# power-management-ctt.net
KiCad netlist of a schematic drawn in Altium Designer
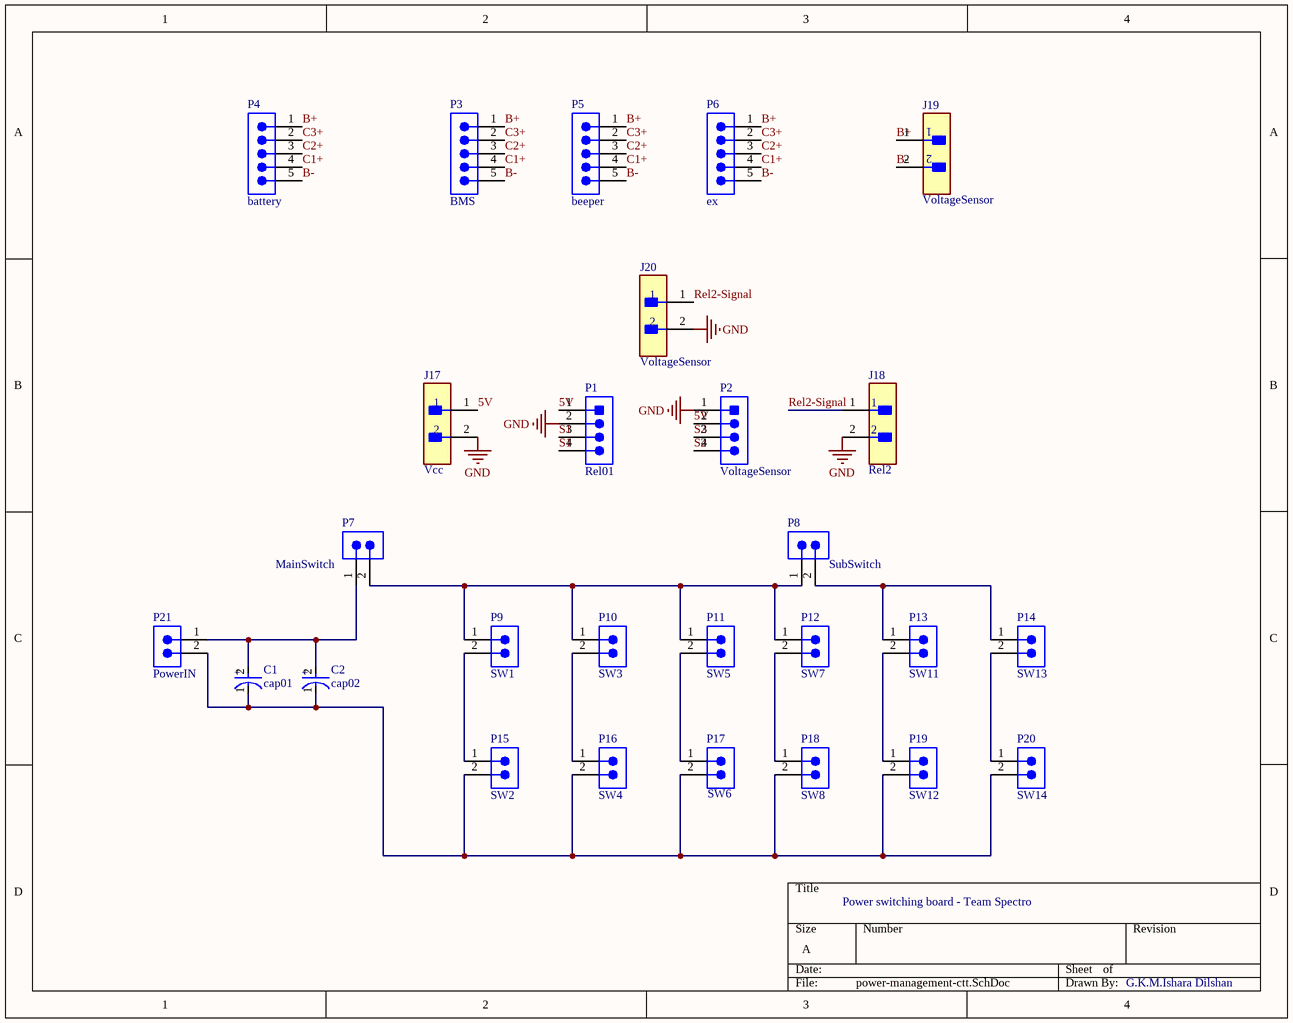
[diagram p0: power-management-ctt.SchDoc]

(export (version "E")
  (design (tool "Eeschema 10.0.6"))
  (components
    (comp (ref "C1")
      (value "cap01")
      (footprint "FP-RAD-TH-D_16_0_5-L_25_2-MFG")
      (description "Aluminum Electrolytic Capacitors (Radial Lead Type) 4700uF ±20% 16V")
      (fields (field (name "TOLERANCE") "20%") (field (name "VOLTAGE") "16V"))
      (libsource (lib "Altium Content Vault") (part "203bc49f2ac43e59fd269a8c329ed05"))
    )
    (comp (ref "C2")
      (value "cap02")
      (footprint "FP-RAD-TH-D_16_0_5-L_25_2-MFG")
      (description "Aluminum Electrolytic Capacitors (Radial Lead Type) 4700uF ±20% 16V")
      (fields (field (name "TOLERANCE") "20%") (field (name "VOLTAGE") "16V"))
      (libsource (lib "Altium Content Vault") (part "203bc49f2ac43e59fd269a8c329ed05"))
    )
    (comp (ref "J17")
      (value "Vcc")
      (footprint "FP-M20-9990245-MFG")
      (description "CONN HEADER VERT 2POS 2.54MM")
      (fields (field (name "VOLTAGE") "50V"))
      (libsource (lib "") (part "3bc925449376181038e59eaffc5286c_1"))
    )
    (comp (ref "J18")
      (value "Rel2")
      (footprint "FP-M20-9990245-MFG")
      (description "CONN HEADER VERT 2POS 2.54MM")
      (fields (field (name "VOLTAGE") "50V"))
      (libsource (lib "Altium Content Vault") (part "3bc925449376181038e59eaffc5286c"))
    )
    (comp (ref "J19")
      (value "VoltageSensor")
      (footprint "FP-M20-9990245-MFG")
      (description "CONN HEADER VERT 2POS 2.54MM")
      (fields (field (name "VOLTAGE") "50V"))
      (libsource (lib "Altium Content Vault") (part "3bc925449376181038e59eaffc5286c"))
    )
    (comp (ref "J20")
      (value "VoltageSensor")
      (footprint "FP-M20-9990245-MFG")
      (description "CONN HEADER VERT 2POS 2.54MM")
      (fields (field (name "VOLTAGE") "50V"))
      (libsource (lib "") (part "3bc925449376181038e59eaffc5286c_1"))
    )
    (comp (ref "P1")
      (value "Rel01")
      (footprint "MOLX-22-27-2041_V")
      (description "Male Header, Pitch 2.54 mm, 1 x 4 Position, Height 11.7 mm, Tail Length 3.56 mm, RoHS, Bulk")
      (fields (field (name "MANUFACTURER") "Molex"))
      (libsource (lib "Altium Content Vault") (part "CN-1P-M-R4"))
    )
    (comp (ref "P2")
      (value "VoltageSensor")
      (footprint "MOLX-22-27-2041_V")
      (description "Male Header, Pitch 2.54 mm, 1 x 4 Position, Height 11.7 mm, Tail Length 3.56 mm, RoHS, Bulk")
      (fields (field (name "MANUFACTURER") "Molex"))
      (libsource (lib "Altium Content Vault") (part "CN-1P-M-R4"))
    )
    (comp (ref "P3")
      (value "BMS")
      (footprint "691311500105")
      (fields (field (name "VOLTAGE") "300V"))
      (libsource (lib "Altium Content Vault") (part "TBL - 1R - 05P - Male"))
    )
    (comp (ref "P4")
      (value "battery")
      (footprint "691311500105")
      (fields (field (name "VOLTAGE") "300V"))
      (libsource (lib "Altium Content Vault") (part "TBL - 1R - 05P - Male"))
    )
    (comp (ref "P5")
      (value "beeper")
      (footprint "691311500105")
      (fields (field (name "VOLTAGE") "300V"))
      (libsource (lib "Altium Content Vault") (part "TBL - 1R - 05P - Male"))
    )
    (comp (ref "P6")
      (value "ex")
      (footprint "691311500105")
      (fields (field (name "VOLTAGE") "300V"))
      (libsource (lib "Altium Content Vault") (part "TBL - 1R - 05P - Male"))
    )
    (comp (ref "P7")
      (value "MainSwitch")
      (footprint "691313410002")
      (fields (field (name "VOLTAGE") "300V"))
      (libsource (lib "Altium Content Vault") (part "TBL - 1R - 02P - Male"))
    )
    (comp (ref "P8")
      (value "SubSwitch")
      (footprint "691313410002")
      (fields (field (name "VOLTAGE") "300V"))
      (libsource (lib "Altium Content Vault") (part "TBL - 1R - 02P - Male"))
    )
    (comp (ref "P9")
      (value "SW1")
      (footprint "691313410002")
      (fields (field (name "VOLTAGE") "300V"))
      (libsource (lib "Altium Content Vault") (part "TBL - 1R - 02P - Male"))
    )
    (comp (ref "P10")
      (value "SW3")
      (footprint "691313410002")
      (fields (field (name "VOLTAGE") "300V"))
      (libsource (lib "Altium Content Vault") (part "TBL - 1R - 02P - Male"))
    )
    (comp (ref "P11")
      (value "SW5")
      (footprint "691313410002")
      (fields (field (name "VOLTAGE") "300V"))
      (libsource (lib "Altium Content Vault") (part "TBL - 1R - 02P - Male"))
    )
    (comp (ref "P12")
      (value "SW7")
      (footprint "691313410002")
      (fields (field (name "VOLTAGE") "300V"))
      (libsource (lib "Altium Content Vault") (part "TBL - 1R - 02P - Male"))
    )
    (comp (ref "P13")
      (value "SW11")
      (footprint "691313410002")
      (fields (field (name "VOLTAGE") "300V"))
      (libsource (lib "Altium Content Vault") (part "TBL - 1R - 02P - Male"))
    )
    (comp (ref "P14")
      (value "SW13")
      (footprint "691313410002")
      (fields (field (name "VOLTAGE") "300V"))
      (libsource (lib "Altium Content Vault") (part "TBL - 1R - 02P - Male"))
    )
    (comp (ref "P15")
      (value "SW2")
      (footprint "691313410002")
      (fields (field (name "VOLTAGE") "300V"))
      (libsource (lib "Altium Content Vault") (part "TBL - 1R - 02P - Male"))
    )
    (comp (ref "P16")
      (value "SW4")
      (footprint "691313410002")
      (fields (field (name "VOLTAGE") "300V"))
      (libsource (lib "Altium Content Vault") (part "TBL - 1R - 02P - Male"))
    )
    (comp (ref "P17")
      (value "SW6")
      (footprint "691313410002")
      (fields (field (name "VOLTAGE") "300V"))
      (libsource (lib "Altium Content Vault") (part "TBL - 1R - 02P - Male"))
    )
    (comp (ref "P18")
      (value "SW8")
      (footprint "691313410002")
      (fields (field (name "VOLTAGE") "300V"))
      (libsource (lib "Altium Content Vault") (part "TBL - 1R - 02P - Male"))
    )
    (comp (ref "P19")
      (value "SW12")
      (footprint "691313410002")
      (fields (field (name "VOLTAGE") "300V"))
      (libsource (lib "Altium Content Vault") (part "TBL - 1R - 02P - Male"))
    )
    (comp (ref "P20")
      (value "SW14")
      (footprint "691313410002")
      (fields (field (name "VOLTAGE") "300V"))
      (libsource (lib "Altium Content Vault") (part "TBL - 1R - 02P - Male"))
    )
    (comp (ref "P21")
      (value "PowerIN")
      (footprint "691313410002")
      (fields (field (name "VOLTAGE") "300V"))
      (libsource (lib "Altium Content Vault") (part "TBL - 1R - 02P - Male"))
    )
  )
  (nets
    (net (code "1") (name "/5V") (class "Default")
      (node (ref "J17") (pin "1") (pinfunction "1_1") (pintype "passive"))
      (node (ref "P1") (pin "1") (pinfunction "1_1") (pintype "passive"))
      (node (ref "P2") (pin "2") (pinfunction "2_2") (pintype "passive"))
    )
    (net (code "2") (name "/B+") (class "Default")
      (node (ref "J19") (pin "1") (pinfunction "1_1") (pintype "passive"))
      (node (ref "P3") (pin "1") (pinfunction "1_1") (pintype "passive"))
      (node (ref "P4") (pin "1") (pinfunction "1_1") (pintype "passive"))
      (node (ref "P5") (pin "1") (pinfunction "1_1") (pintype "passive"))
      (node (ref "P6") (pin "1") (pinfunction "1_1") (pintype "passive"))
    )
    (net (code "3") (name "/B-") (class "Default")
      (node (ref "J19") (pin "2") (pinfunction "2_2") (pintype "passive"))
      (node (ref "P3") (pin "5") (pinfunction "5_5") (pintype "passive"))
      (node (ref "P4") (pin "5") (pinfunction "5_5") (pintype "passive"))
      (node (ref "P5") (pin "5") (pinfunction "5_5") (pintype "passive"))
      (node (ref "P6") (pin "5") (pinfunction "5_5") (pintype "passive"))
    )
    (net (code "4") (name "/C1+") (class "Default")
      (node (ref "P3") (pin "4") (pinfunction "4_4") (pintype "passive"))
      (node (ref "P4") (pin "4") (pinfunction "4_4") (pintype "passive"))
      (node (ref "P5") (pin "4") (pinfunction "4_4") (pintype "passive"))
      (node (ref "P6") (pin "4") (pinfunction "4_4") (pintype "passive"))
    )
    (net (code "5") (name "/C2+") (class "Default")
      (node (ref "P3") (pin "3") (pinfunction "3_3") (pintype "passive"))
      (node (ref "P4") (pin "3") (pinfunction "3_3") (pintype "passive"))
      (node (ref "P5") (pin "3") (pinfunction "3_3") (pintype "passive"))
      (node (ref "P6") (pin "3") (pinfunction "3_3") (pintype "passive"))
    )
    (net (code "6") (name "/C3+") (class "Default")
      (node (ref "P3") (pin "2") (pinfunction "2_2") (pintype "passive"))
      (node (ref "P4") (pin "2") (pinfunction "2_2") (pintype "passive"))
      (node (ref "P5") (pin "2") (pinfunction "2_2") (pintype "passive"))
      (node (ref "P6") (pin "2") (pinfunction "2_2") (pintype "passive"))
    )
    (net (code "7") (name "/Rel2-Signal") (class "Default")
      (node (ref "J18") (pin "1") (pinfunction "1_1") (pintype "passive"))
      (node (ref "J20") (pin "1") (pinfunction "1_1") (pintype "passive"))
    )
    (net (code "8") (name "/S1") (class "Default")
      (node (ref "P1") (pin "3") (pinfunction "3_3") (pintype "passive"))
      (node (ref "P1") (pin "4") (pinfunction "4_4") (pintype "passive"))
    )
    (net (code "9") (name "/S2") (class "Default")
      (node (ref "P2") (pin "3") (pinfunction "3_3") (pintype "passive"))
      (node (ref "P2") (pin "4") (pinfunction "4_4") (pintype "passive"))
    )
    (net (code "10") (name "GND") (class "Default")
      (node (ref "J17") (pin "2") (pinfunction "2_2") (pintype "passive"))
      (node (ref "J18") (pin "2") (pinfunction "2_2") (pintype "passive"))
      (node (ref "J20") (pin "2") (pinfunction "2_2") (pintype "passive"))
      (node (ref "P1") (pin "2") (pinfunction "2_2") (pintype "passive"))
      (node (ref "P2") (pin "1") (pinfunction "1_1") (pintype "passive"))
    )
    (net (code "11") (name "Net-(C1-A)") (class "Default")
      (node (ref "C1") (pin "2") (pinfunction "A_2") (pintype "passive"))
      (node (ref "C2") (pin "2") (pinfunction "A_2") (pintype "passive"))
      (node (ref "P21") (pin "1") (pinfunction "1_1") (pintype "passive"))
      (node (ref "P7") (pin "1") (pinfunction "1_1") (pintype "passive"))
    )
    (net (code "12") (name "Net-(C1-C)") (class "Default")
      (node (ref "C1") (pin "1") (pinfunction "C_1") (pintype "passive"))
      (node (ref "C2") (pin "1") (pinfunction "C_1") (pintype "passive"))
      (node (ref "P15") (pin "2") (pinfunction "2_2") (pintype "passive"))
      (node (ref "P16") (pin "2") (pinfunction "2_2") (pintype "passive"))
      (node (ref "P17") (pin "2") (pinfunction "2_2") (pintype "passive"))
      (node (ref "P18") (pin "2") (pinfunction "2_2") (pintype "passive"))
      (node (ref "P19") (pin "2") (pinfunction "2_2") (pintype "passive"))
      (node (ref "P20") (pin "2") (pinfunction "2_2") (pintype "passive"))
      (node (ref "P21") (pin "2") (pinfunction "2_2") (pintype "passive"))
    )
    (net (code "13") (name "Net-(P10-Pad1)") (class "Default")
      (node (ref "P10") (pin "1") (pinfunction "1_1") (pintype "passive"))
      (node (ref "P11") (pin "1") (pinfunction "1_1") (pintype "passive"))
      (node (ref "P12") (pin "1") (pinfunction "1_1") (pintype "passive"))
      (node (ref "P7") (pin "2") (pinfunction "2_2") (pintype "passive"))
      (node (ref "P8") (pin "1") (pinfunction "1_1") (pintype "passive"))
      (node (ref "P9") (pin "1") (pinfunction "1_1") (pintype "passive"))
    )
    (net (code "14") (name "Net-(P10-Pad2)") (class "Default")
      (node (ref "P10") (pin "2") (pinfunction "2_2") (pintype "passive"))
      (node (ref "P16") (pin "1") (pinfunction "1_1") (pintype "passive"))
    )
    (net (code "15") (name "Net-(P11-Pad2)") (class "Default")
      (node (ref "P11") (pin "2") (pinfunction "2_2") (pintype "passive"))
      (node (ref "P17") (pin "1") (pinfunction "1_1") (pintype "passive"))
    )
    (net (code "16") (name "Net-(P12-Pad2)") (class "Default")
      (node (ref "P12") (pin "2") (pinfunction "2_2") (pintype "passive"))
      (node (ref "P18") (pin "1") (pinfunction "1_1") (pintype "passive"))
    )
    (net (code "17") (name "Net-(P13-Pad1)") (class "Default")
      (node (ref "P13") (pin "1") (pinfunction "1_1") (pintype "passive"))
      (node (ref "P14") (pin "1") (pinfunction "1_1") (pintype "passive"))
      (node (ref "P8") (pin "2") (pinfunction "2_2") (pintype "passive"))
    )
    (net (code "18") (name "Net-(P13-Pad2)") (class "Default")
      (node (ref "P13") (pin "2") (pinfunction "2_2") (pintype "passive"))
      (node (ref "P19") (pin "1") (pinfunction "1_1") (pintype "passive"))
    )
    (net (code "19") (name "Net-(P14-Pad2)") (class "Default")
      (node (ref "P14") (pin "2") (pinfunction "2_2") (pintype "passive"))
      (node (ref "P20") (pin "1") (pinfunction "1_1") (pintype "passive"))
    )
    (net (code "20") (name "Net-(P15-Pad1)") (class "Default")
      (node (ref "P15") (pin "1") (pinfunction "1_1") (pintype "passive"))
      (node (ref "P9") (pin "2") (pinfunction "2_2") (pintype "passive"))
    )
  )
)
